# Power.net
KiCad netlist of a schematic drawn in Altium Designer
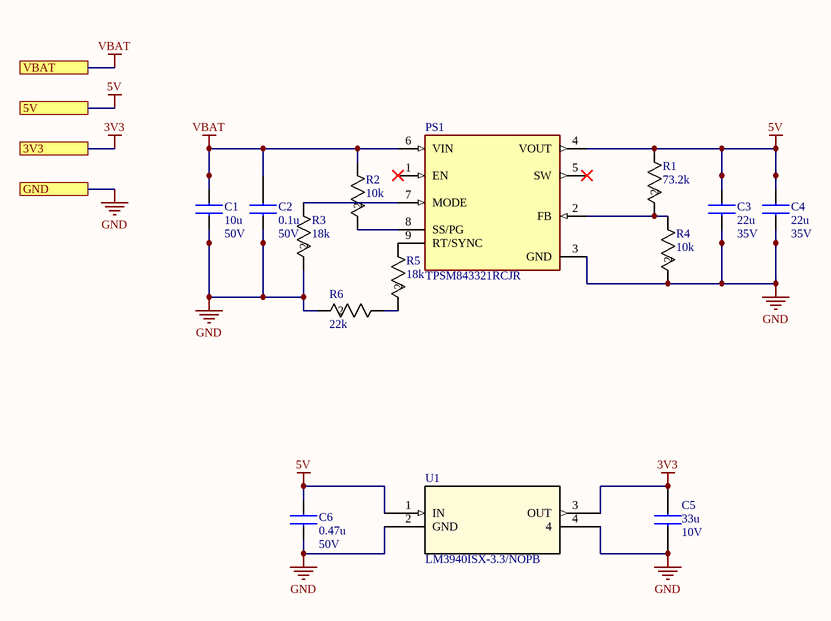
[diagram p0: Power.SchDoc]

(export (version "E")
  (design (tool "Eeschema 10.0.6"))
  (components
    (comp (ref "C1")
      (value "10u")
      (footprint "CAPC2012X145N")
      (description "Multilayer Ceramic Chip Capacitors, Capacitance=10?F, LxWxT:2x1.25x1.25mm")
      (fields
        (field (name "MOUSER PART NUMBER") "810-C2012X5R1H106K12")
        (field (name "MANUFACTURER_PART_NUMBER") "C2012X5R1H106K125AC")
        (field (name "RATED VOLTAGE") "50V")
      )
      (libsource (lib "Caps") (part "C2012X5R1H106K125AC"))
    )
    (comp (ref "C2")
      (value "0.1u")
      (footprint "CAPC2012X145N")
      (description "Multilayer Ceramic Chip Capacitors, Capacitance=0.1u")
      (fields
        (field (name "MANUFACTURER_PART_NUMBER") "KAM21BR71H104JM")
        (field (name "RATED VOLTAGE") "50V")
      )
      (libsource (lib "Caps") (part "KAM21BR71H104JM"))
    )
    (comp (ref "C3")
      (value "22u")
      (footprint "CAPC2012X145N")
      (description "Multilayer Ceramic Chip Capacitors, Capacitance=22u")
      (fields
        (field (name "MANUFACTURER_PART_NUMBER") "C2012X5R1V226M125AC")
        (field (name "RATED VOLTAGE") "35V")
      )
      (libsource (lib "Caps") (part "C2012X5R1V226M125AC"))
    )
    (comp (ref "C4")
      (value "22u")
      (footprint "CAPC2012X145N")
      (description "Multilayer Ceramic Chip Capacitors, Capacitance=22u")
      (fields
        (field (name "MANUFACTURER_PART_NUMBER") "C2012X5R1V226M125AC")
        (field (name "RATED VOLTAGE") "35V")
      )
      (libsource (lib "Caps") (part "C2012X5R1V226M125AC"))
    )
    (comp (ref "C5")
      (value "33u")
      (footprint "CAPC2012X145N")
      (description "Multilayer Ceramic Chip Capacitors, Capacitance=33u")
      (fields
        (field (name "MANUFACTURER_PART_NUMBER") "C2012X5R1A336M125AC")
        (field (name "RATED VOLTAGE") "10V")
      )
      (libsource (lib "Caps") (part "C2012X5R1A336M125AC"))
    )
    (comp (ref "C6")
      (value "0.47u")
      (footprint "CAPC2012X145N")
      (description "Multilayer Ceramic Chip Capacitors, Capacitance=0.47u")
      (fields
        (field (name "MANUFACTURER_PART_NUMBER") "GCM21BR71H474KA55K")
        (field (name "RATED VOLTAGE") "50V")
      )
      (libsource (lib "Caps") (part "GCM21BR71H474KA55K"))
    )
    (comp (ref "PS1")
      (value "TPSM843321RCJR")
      (footprint "MODULE_TPSM843321RCJR")
      (description "Non-Isolated PoL Module DC DC Converter 1 Output 5V 3A 3.8V - 18V Input")
      (fields (field (name "MF") "Texas Instruments"))
      (libsource (lib "TPSM843321RCJR") (part "TPSM843321RCJR"))
    )
    (comp (ref "R1")
      (value "73.2k")
      (footprint "RC0805N_YAG")
      (description "RES 0805 73.2k 1% 1/8W")
      (fields (field (name "MANUFACTURER_PART_NUMBER") "RC0805FR-0773K2L") (field (name "TOLERANCE") "1%"))
      (libsource (lib "Resistors") (part "RC0805FR-0773K2L"))
    )
    (comp (ref "R2")
      (value "10k")
      (footprint "RC0805N_YAG")
      (description "RES 0805 10k 1% 1/8W")
      (fields (field (name "MANUFACTURER_PART_NUMBER") "RC0805FR-0710KL") (field (name "TOLERANCE") "1%"))
      (libsource (lib "Resistors") (part "RC0805FR-0710KL"))
    )
    (comp (ref "R3")
      (value "18k")
      (footprint "RC0805N_YAG")
      (description "RES 0805 18k 1% 1/8W")
      (fields (field (name "MANUFACTURER_PART_NUMBER") "RC0805FR-0718KL") (field (name "TOLERANCE") "1%"))
      (libsource (lib "Resistors") (part "RC0805FR-0718KL"))
    )
    (comp (ref "R4")
      (value "10k")
      (footprint "RC0805N_YAG")
      (description "RES 0805 10k 1% 1/8W")
      (fields (field (name "MANUFACTURER_PART_NUMBER") "RC0805FR-0710KL") (field (name "TOLERANCE") "1%"))
      (libsource (lib "Resistors") (part "RC0805FR-0710KL"))
    )
    (comp (ref "R5")
      (value "18k")
      (footprint "RC0805N_YAG")
      (description "RES 0805 18k 1% 1/8W")
      (fields (field (name "MANUFACTURER_PART_NUMBER") "RC0805FR-0718KL") (field (name "TOLERANCE") "1%"))
      (libsource (lib "Resistors") (part "RC0805FR-0718KL"))
    )
    (comp (ref "R6")
      (value "22k")
      (footprint "RC0805N_YAG")
      (description "RES 0805 22k 1% 1/8W")
      (fields (field (name "MANUFACTURER_PART_NUMBER") "RC0805FR-0722KL") (field (name "TOLERANCE") "1%"))
      (libsource (lib "Resistors") (part "RC0805FR-0722KL"))
    )
    (comp (ref "U1")
      (value "LM3940ISX-3.3/NOPB")
      (footprint "TS3B")
      (description "1-A, low-dropout voltage regulator for 5-V to 3.3-V conversion 3-DDPAK/TO-263 -40 to 125")
      (fields (field (name "COPYRIGHT") "Copyright (C) 2025 Ultra Librarian. All rights reserved."))
      (libsource (lib "LM3940ISX-3P3NOPB") (part "LM3940ISX-3.3NOPB"))
    )
  )
  (nets
    (net (code "1") (name "3V3") (class "Default")
      (node (ref "C5") (pin "2") (pinfunction "2_2") (pintype "passive"))
      (node (ref "U1") (pin "3") (pinfunction "OUT_3") (pintype "output"))
    )
    (net (code "2") (name "5V") (class "Default")
      (node (ref "C3") (pin "2") (pinfunction "2_2") (pintype "passive"))
      (node (ref "C4") (pin "2") (pinfunction "2_2") (pintype "passive"))
      (node (ref "C6") (pin "2") (pinfunction "2_2") (pintype "passive"))
      (node (ref "PS1") (pin "4") (pinfunction "VOUT_4") (pintype "output"))
      (node (ref "R1") (pin "1") (pinfunction "1_1") (pintype "passive"))
      (node (ref "U1") (pin "1") (pinfunction "IN_1") (pintype "input"))
    )
    (net (code "3") (name "GND") (class "Default")
      (node (ref "C1") (pin "1") (pinfunction "1_1") (pintype "passive"))
      (node (ref "C2") (pin "1") (pinfunction "1_1") (pintype "passive"))
      (node (ref "C3") (pin "1") (pinfunction "1_1") (pintype "passive"))
      (node (ref "C4") (pin "1") (pinfunction "1_1") (pintype "passive"))
      (node (ref "C5") (pin "1") (pinfunction "1_1") (pintype "passive"))
      (node (ref "C6") (pin "1") (pinfunction "1_1") (pintype "passive"))
      (node (ref "PS1") (pin "3") (pinfunction "GND_3") (pintype "power_in"))
      (node (ref "R3") (pin "2") (pinfunction "2_2") (pintype "passive"))
      (node (ref "R4") (pin "2") (pinfunction "2_2") (pintype "passive"))
      (node (ref "R6") (pin "2") (pinfunction "2_2") (pintype "passive"))
      (node (ref "U1") (pin "2") (pinfunction "GND_2") (pintype "passive"))
      (node (ref "U1") (pin "4") (pinfunction "4_4") (pintype "passive"))
    )
    (net (code "4") (name "Net-(PS1-FB)") (class "Default")
      (node (ref "PS1") (pin "2") (pinfunction "FB_2") (pintype "input"))
      (node (ref "R1") (pin "2") (pinfunction "2_2") (pintype "passive"))
      (node (ref "R4") (pin "1") (pinfunction "1_1") (pintype "passive"))
    )
    (net (code "5") (name "Net-(PS1-MODE)") (class "Default")
      (node (ref "PS1") (pin "7") (pinfunction "MODE_7") (pintype "input"))
      (node (ref "R3") (pin "1") (pinfunction "1_1") (pintype "passive"))
    )
    (net (code "6") (name "Net-(PS1-RT{slash}SYNC)") (class "Default")
      (node (ref "PS1") (pin "9") (pinfunction "RT/SYNC_9") (pintype "passive"))
      (node (ref "R5") (pin "1") (pinfunction "1_1") (pintype "passive"))
    )
    (net (code "7") (name "Net-(PS1-SS{slash}PG)") (class "Default")
      (node (ref "PS1") (pin "8") (pinfunction "SS/PG_8") (pintype "passive"))
      (node (ref "R2") (pin "2") (pinfunction "2_2") (pintype "passive"))
    )
    (net (code "8") (name "Net-(R5-Pad2)") (class "Default")
      (node (ref "R5") (pin "2") (pinfunction "2_2") (pintype "passive"))
      (node (ref "R6") (pin "1") (pinfunction "1_1") (pintype "passive"))
    )
    (net (code "9") (name "VBAT") (class "Default")
      (node (ref "C1") (pin "2") (pinfunction "2_2") (pintype "passive"))
      (node (ref "C2") (pin "2") (pinfunction "2_2") (pintype "passive"))
      (node (ref "PS1") (pin "6") (pinfunction "VIN_6") (pintype "input"))
      (node (ref "R2") (pin "1") (pinfunction "1_1") (pintype "passive"))
    )
    (net (code "10") (name "unconnected-(PS1-EN-Pad1)") (class "Default")
      (node (ref "PS1") (pin "1") (pinfunction "EN_1") (pintype "input+no_connect"))
    )
    (net (code "11") (name "unconnected-(PS1-SW-Pad5)") (class "Default")
      (node (ref "PS1") (pin "5") (pinfunction "SW_5") (pintype "output+no_connect"))
    )
  )
)
